# IM920sL.net
KiCad netlist of a schematic drawn in EAGLE
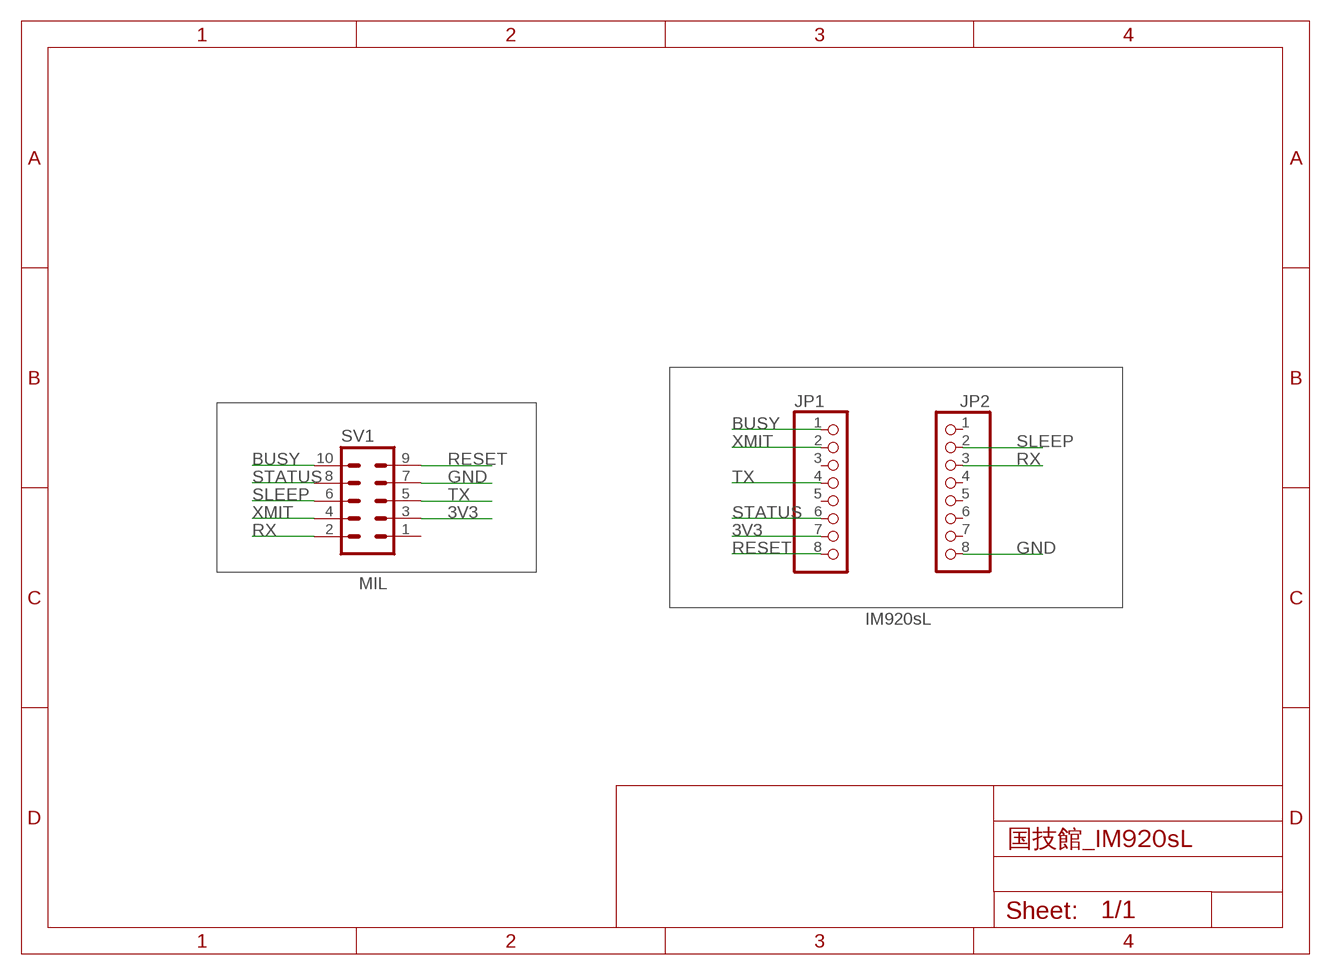
[diagram p0: schematic, sheet 1]

(export (version "E")
  (design (tool "Eeschema 10.0.6"))
  (components
    (comp (ref "JP1")
      (value "PINHD-1X8")
      (footprint "eagle-import:1X08")
      (libsource (lib "eagle-import") (part "PINHD-1X8"))
    )
    (comp (ref "JP2")
      (value "PINHD-1X8")
      (footprint "eagle-import:1X08")
      (libsource (lib "eagle-import") (part "PINHD-1X8"))
    )
    (comp (ref "SV1")
      (value "ML10")
      (footprint "eagle-import:ML10")
      (libsource (lib "eagle-import") (part "ML10"))
    )
  )
  (nets
    (net (code "1") (name "/3V3") (class "Default")
      (node (ref "JP1") (pin "7") (pinfunction "7_7") (pintype "passive"))
      (node (ref "SV1") (pin "3") (pinfunction "3_3") (pintype "passive"))
    )
    (net (code "2") (name "/BUSY") (class "Default")
      (node (ref "JP1") (pin "1") (pinfunction "1_1") (pintype "passive"))
      (node (ref "SV1") (pin "10") (pinfunction "10_10") (pintype "passive"))
    )
    (net (code "3") (name "/GND") (class "Default")
      (node (ref "JP2") (pin "8") (pinfunction "8_8") (pintype "passive"))
      (node (ref "SV1") (pin "7") (pinfunction "7_7") (pintype "passive"))
    )
    (net (code "4") (name "/RESET") (class "Default")
      (node (ref "JP1") (pin "8") (pinfunction "8_8") (pintype "passive"))
      (node (ref "SV1") (pin "9") (pinfunction "9_9") (pintype "passive"))
    )
    (net (code "5") (name "/RX") (class "Default")
      (node (ref "JP2") (pin "3") (pinfunction "3_3") (pintype "passive"))
      (node (ref "SV1") (pin "2") (pinfunction "2_2") (pintype "passive"))
    )
    (net (code "6") (name "/SLEEP") (class "Default")
      (node (ref "JP2") (pin "2") (pinfunction "2_2") (pintype "passive"))
      (node (ref "SV1") (pin "6") (pinfunction "6_6") (pintype "passive"))
    )
    (net (code "7") (name "/STATUS") (class "Default")
      (node (ref "JP1") (pin "6") (pinfunction "6_6") (pintype "passive"))
      (node (ref "SV1") (pin "8") (pinfunction "8_8") (pintype "passive"))
    )
    (net (code "8") (name "/TX") (class "Default")
      (node (ref "JP1") (pin "4") (pinfunction "4_4") (pintype "passive"))
      (node (ref "SV1") (pin "5") (pinfunction "5_5") (pintype "passive"))
    )
    (net (code "9") (name "/XMIT") (class "Default")
      (node (ref "JP1") (pin "2") (pinfunction "2_2") (pintype "passive"))
      (node (ref "SV1") (pin "4") (pinfunction "4_4") (pintype "passive"))
    )
    (net (code "10") (name "unconnected-(JP1-Pad3)") (class "Default")
      (node (ref "JP1") (pin "3") (pinfunction "3_3") (pintype "passive"))
    )
    (net (code "11") (name "unconnected-(JP1-Pad5)") (class "Default")
      (node (ref "JP1") (pin "5") (pinfunction "5_5") (pintype "passive"))
    )
    (net (code "12") (name "unconnected-(JP2-Pad1)") (class "Default")
      (node (ref "JP2") (pin "1") (pinfunction "1_1") (pintype "passive"))
    )
    (net (code "13") (name "unconnected-(JP2-Pad4)") (class "Default")
      (node (ref "JP2") (pin "4") (pinfunction "4_4") (pintype "passive"))
    )
    (net (code "14") (name "unconnected-(JP2-Pad5)") (class "Default")
      (node (ref "JP2") (pin "5") (pinfunction "5_5") (pintype "passive"))
    )
    (net (code "15") (name "unconnected-(JP2-Pad6)") (class "Default")
      (node (ref "JP2") (pin "6") (pinfunction "6_6") (pintype "passive"))
    )
    (net (code "16") (name "unconnected-(JP2-Pad7)") (class "Default")
      (node (ref "JP2") (pin "7") (pinfunction "7_7") (pintype "passive"))
    )
    (net (code "17") (name "unconnected-(SV1-Pad1)") (class "Default")
      (node (ref "SV1") (pin "1") (pinfunction "1_1") (pintype "passive"))
    )
  )
)
